# TOP.net
KiCad netlist of a schematic drawn in Altium Designer
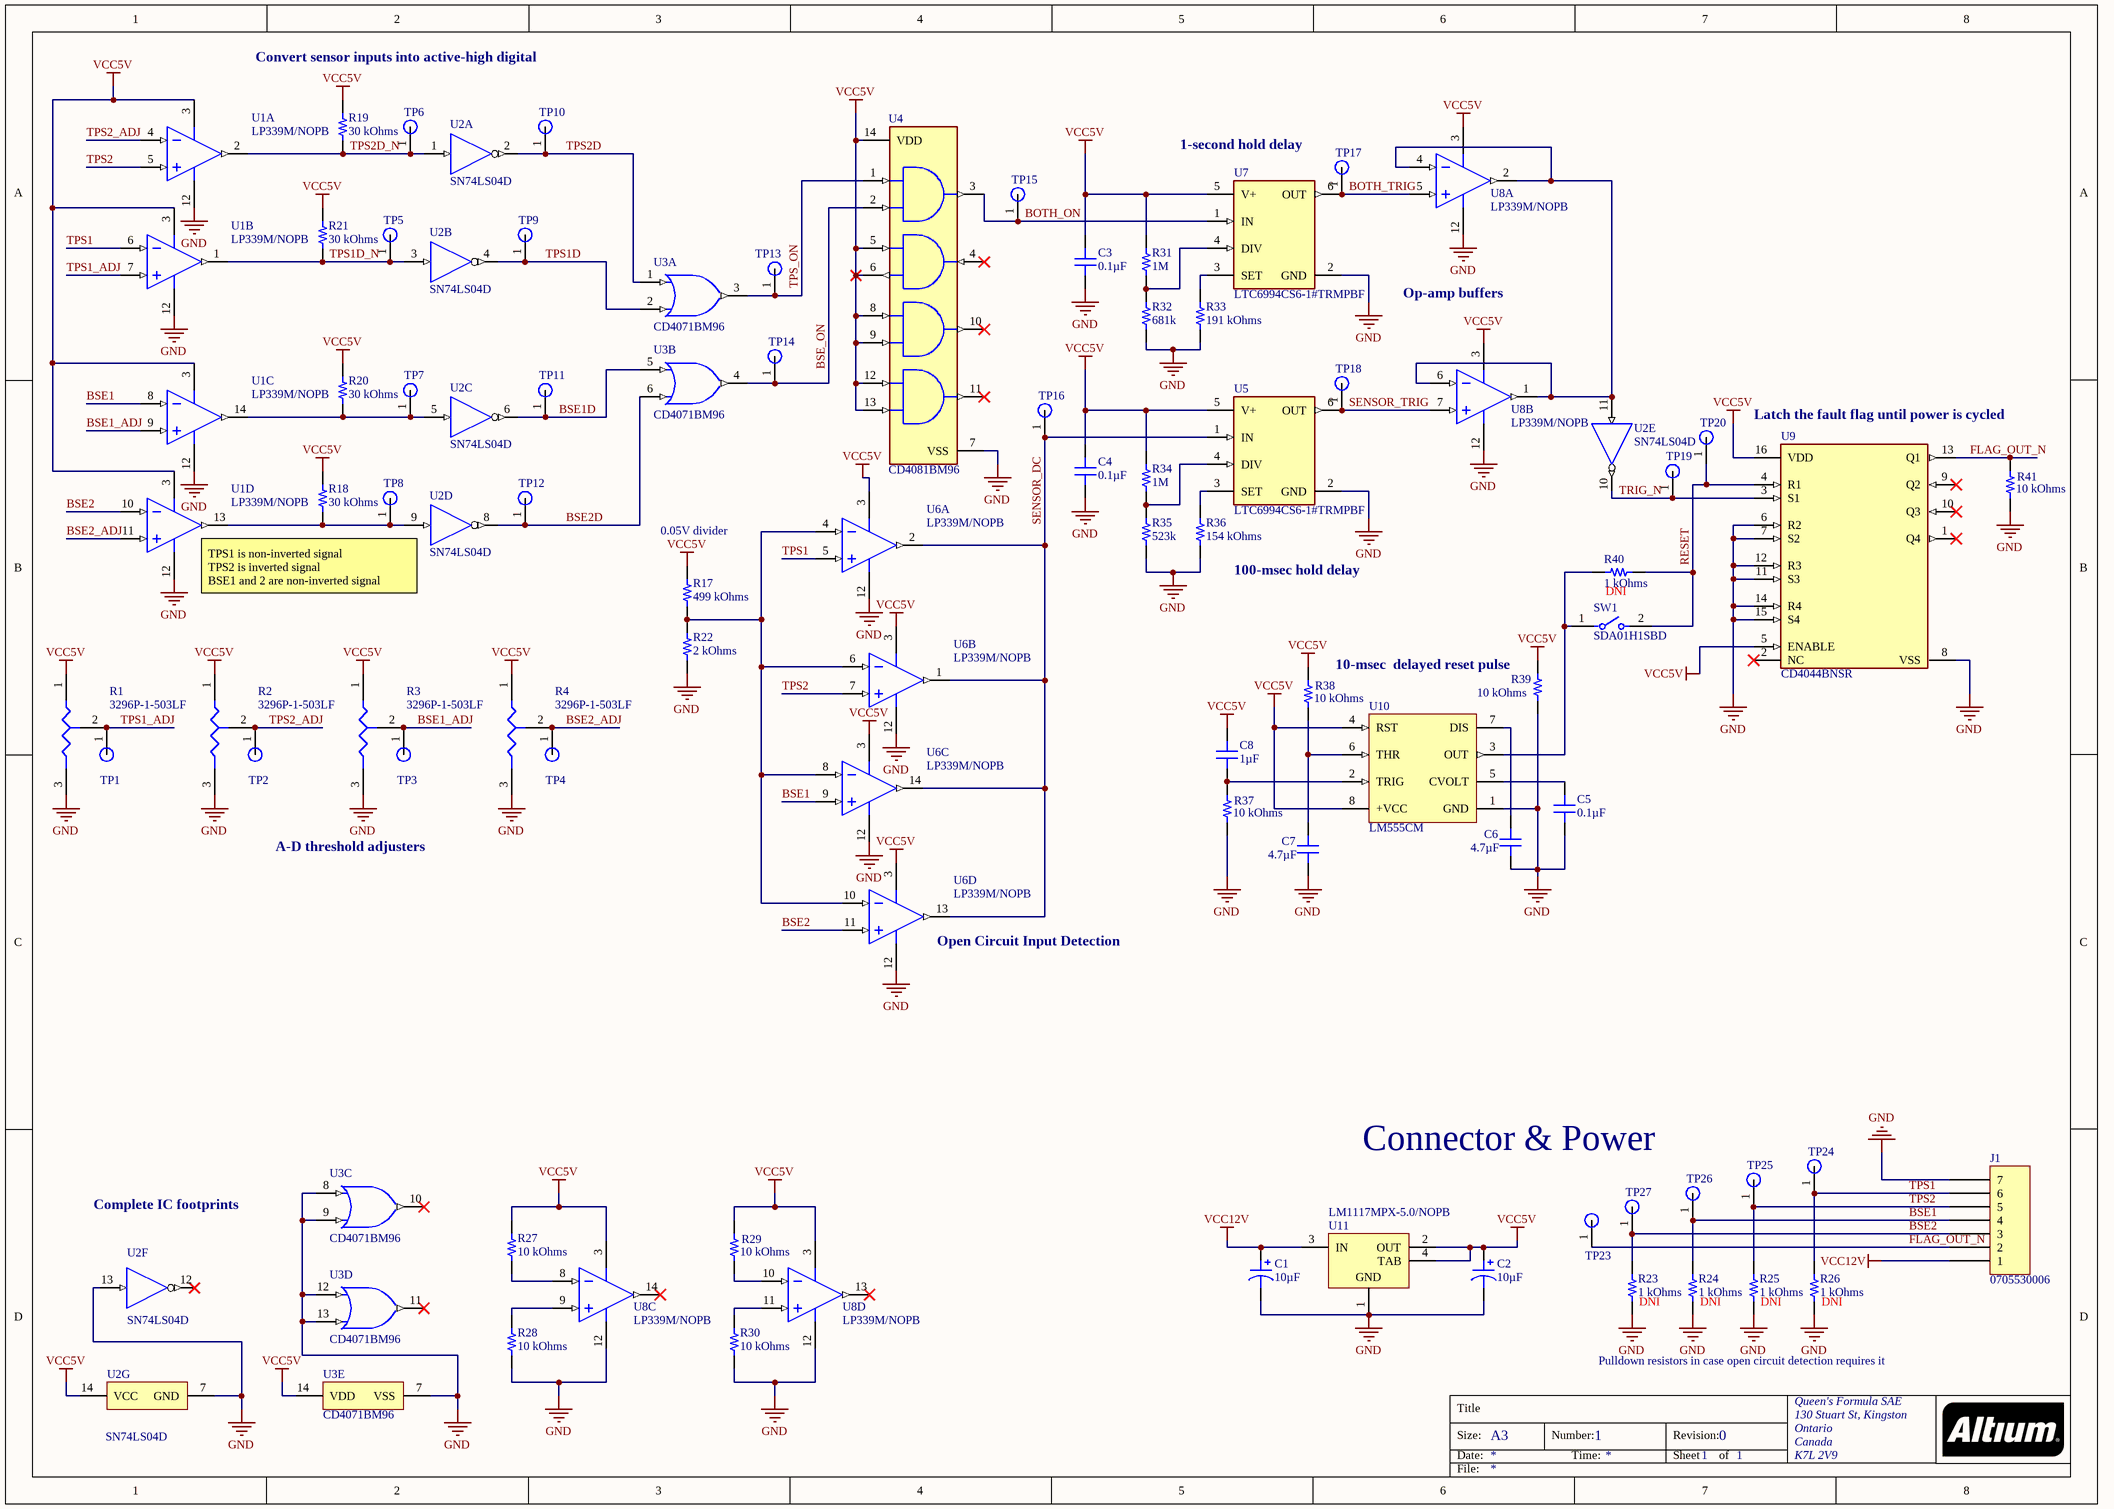
[diagram p0: TOP.SchDoc]

(export (version "E")
  (design (tool "Eeschema 10.0.6"))
  (components
    (comp (ref "C1")
      (value "10µF")
      (footprint "CAP ALSMD 5.3MM H5.4MM")
      (description "CAP ALUM 10UF 20% 50V SMD")
      (fields
        (field (name "PART NUMBER") "EEE-1HA100WR")
        (field (name "MANUFACTURER") "Panasonic Electronic Components")
      )
      (libsource (lib "Celestial Altium Library - altium_library") (part "Polarised Capacitor"))
    )
    (comp (ref "C2")
      (value "10µF")
      (footprint "CAP ALSMD 5.3MM H5.4MM")
      (description "CAP ALUM 10UF 20% 50V SMD")
      (fields
        (field (name "PART NUMBER") "EEE-1HA100WR")
        (field (name "MANUFACTURER") "Panasonic Electronic Components")
      )
      (libsource (lib "Celestial Altium Library - altium_library") (part "Polarised Capacitor"))
    )
    (comp (ref "C3")
      (value "0.1µF")
      (footprint "CAP 0805_2012")
      (description "CAP CER 0.1UF 25V X7R 0805")
      (fields
        (field (name "PART NUMBER") "VJ0805Y104KXXCW1BC")
        (field (name "MANUFACTURER") "Vishay Vitramon")
      )
      (libsource (lib "Celestial Altium Library - altium_library") (part "Capacitor"))
    )
    (comp (ref "C4")
      (value "0.1µF")
      (footprint "CAP 0805_2012")
      (description "CAP CER 0.1UF 25V X7R 0805")
      (fields
        (field (name "PART NUMBER") "VJ0805Y104KXXCW1BC")
        (field (name "MANUFACTURER") "Vishay Vitramon")
      )
      (libsource (lib "Celestial Altium Library - altium_library") (part "Capacitor"))
    )
    (comp (ref "C5")
      (value "0.1µF")
      (footprint "CAP 0805_2012")
      (description "CAP CER 0.1UF 25V X7R 0805")
      (fields
        (field (name "PART NUMBER") "VJ0805Y104KXXCW1BC")
        (field (name "MANUFACTURER") "Vishay Vitramon")
      )
      (libsource (lib "Celestial Altium Library - altium_library") (part "Capacitor"))
    )
    (comp (ref "C6")
      (value "4.7µF")
      (footprint "CAP 0805_2012")
      (description "CAP CER 4.7UF 25V X5R 0805")
      (fields (field (name "PART NUMBER") "TMK212BBJ475KD-T") (field (name "MANUFACTURER") "Taiyo Yuden"))
      (libsource (lib "Celestial Altium Library - altium_library") (part "Capacitor"))
    )
    (comp (ref "C7")
      (value "4.7µF")
      (footprint "CAP 0805_2012")
      (description "CAP CER 4.7UF 25V X5R 0805")
      (fields (field (name "PART NUMBER") "TMK212BBJ475KD-T") (field (name "MANUFACTURER") "Taiyo Yuden"))
      (libsource (lib "Celestial Altium Library - altium_library") (part "Capacitor"))
    )
    (comp (ref "C8")
      (value "1µF")
      (footprint "CAP 0805_2012")
      (description "CAP CER 1UF 25V X7R 0805")
      (fields
        (field (name "PART NUMBER") "VJ0805Y105KXXTW1BC")
        (field (name "MANUFACTURER") "Vishay Vitramon")
      )
      (libsource (lib "Celestial Altium Library - altium_library") (part "Capacitor"))
    )
    (comp (ref "J1")
      (value "0705530006")
      (footprint "MOLEX SDA-70553-7PIN")
      (description "CONN HEADER R/A 7POS 2.54MM")
      (fields (field (name "MANUFACTURER") "Molex"))
      (libsource (lib "Celestial Altium Library - altium_library") (part "7 Pin"))
    )
    (comp (ref "R1")
      (value "3296P-1-503LF")
      (footprint "3296P-1-503LF-Footprint-1")
      (description "50k 10% Trimmer Potentiometer 25-Turn Cermet")
      (fields (field (name "TOLERANCE") "10%"))
      (libsource (lib "Queens University - FSAE") (part "3296P-1-503LF"))
    )
    (comp (ref "R2")
      (value "3296P-1-503LF")
      (footprint "3296P-1-503LF-Footprint-1")
      (description "50k 10% Trimmer Potentiometer 25-Turn Cermet")
      (fields (field (name "TOLERANCE") "10%"))
      (libsource (lib "Queens University - FSAE") (part "3296P-1-503LF"))
    )
    (comp (ref "R3")
      (value "3296P-1-503LF")
      (footprint "3296P-1-503LF-Footprint-1")
      (description "50k 10% Trimmer Potentiometer 25-Turn Cermet")
      (fields (field (name "TOLERANCE") "10%"))
      (libsource (lib "Queens University - FSAE") (part "3296P-1-503LF"))
    )
    (comp (ref "R4")
      (value "3296P-1-503LF")
      (footprint "3296P-1-503LF-Footprint-1")
      (description "50k 10% Trimmer Potentiometer 25-Turn Cermet")
      (fields (field (name "TOLERANCE") "10%"))
      (libsource (lib "Queens University - FSAE") (part "3296P-1-503LF"))
    )
    (comp (ref "R17")
      (value "499 kOhms")
      (footprint "RES 0805_2012")
      (description "RES SMD 499K OHM 1% 1/8W 0805")
      (fields (field (name "PART NUMBER") "RC0805FR-07499KL") (field (name "MANUFACTURER") "Yageo"))
      (libsource (lib "Celestial Altium Library - altium_library") (part "Resistor"))
    )
    (comp (ref "R18")
      (value "30 kOhms")
      (footprint "RES 0805_2012")
      (description "RES SMD 30K OHM 0.5% 1/8W 0805")
      (fields (field (name "PART NUMBER") "RT0805DRD0730KL") (field (name "MANUFACTURER") "Yageo"))
      (libsource (lib "Celestial Altium Library - altium_library") (part "Resistor"))
    )
    (comp (ref "R19")
      (value "30 kOhms")
      (footprint "RES 0805_2012")
      (description "RES SMD 30K OHM 0.5% 1/8W 0805")
      (fields (field (name "PART NUMBER") "RT0805DRD0730KL") (field (name "MANUFACTURER") "Yageo"))
      (libsource (lib "Celestial Altium Library - altium_library") (part "Resistor"))
    )
    (comp (ref "R20")
      (value "30 kOhms")
      (footprint "RES 0805_2012")
      (description "RES SMD 30K OHM 0.5% 1/8W 0805")
      (fields (field (name "PART NUMBER") "RT0805DRD0730KL") (field (name "MANUFACTURER") "Yageo"))
      (libsource (lib "Celestial Altium Library - altium_library") (part "Resistor"))
    )
    (comp (ref "R21")
      (value "30 kOhms")
      (footprint "RES 0805_2012")
      (description "RES SMD 30K OHM 0.5% 1/8W 0805")
      (fields (field (name "PART NUMBER") "RT0805DRD0730KL") (field (name "MANUFACTURER") "Yageo"))
      (libsource (lib "Celestial Altium Library - altium_library") (part "Resistor"))
    )
    (comp (ref "R22")
      (value "2 kOhms")
      (footprint "RES 0805_2012")
      (description "RES SMD 2K OHM 1% 1/8W 0805")
      (fields (field (name "PART NUMBER") "RC0805FR-072KL") (field (name "MANUFACTURER") "Yageo"))
      (libsource (lib "Celestial Altium Library - altium_library") (part "Resistor"))
    )
    (comp (ref "R23")
      (value "1 kOhms")
      (footprint "RES 0805_2012")
      (description "RES 1K OHM 0.1% 1/10W 0805")
      (fields
        (field (name "PART NUMBER") "RNCS0805BKE1K00")
        (field (name "MANUFACTURER") "Stackpole Electronics Inc")
      )
      (libsource (lib "Celestial Altium Library - altium_library") (part "Resistor"))
    )
    (comp (ref "R24")
      (value "1 kOhms")
      (footprint "RES 0805_2012")
      (description "RES 1K OHM 0.1% 1/10W 0805")
      (fields
        (field (name "PART NUMBER") "RNCS0805BKE1K00")
        (field (name "MANUFACTURER") "Stackpole Electronics Inc")
      )
      (libsource (lib "Celestial Altium Library - altium_library") (part "Resistor"))
    )
    (comp (ref "R25")
      (value "1 kOhms")
      (footprint "RES 0805_2012")
      (description "RES 1K OHM 0.1% 1/10W 0805")
      (fields
        (field (name "PART NUMBER") "RNCS0805BKE1K00")
        (field (name "MANUFACTURER") "Stackpole Electronics Inc")
      )
      (libsource (lib "Celestial Altium Library - altium_library") (part "Resistor"))
    )
    (comp (ref "R26")
      (value "1 kOhms")
      (footprint "RES 0805_2012")
      (description "RES 1K OHM 0.1% 1/10W 0805")
      (fields
        (field (name "PART NUMBER") "RNCS0805BKE1K00")
        (field (name "MANUFACTURER") "Stackpole Electronics Inc")
      )
      (libsource (lib "Celestial Altium Library - altium_library") (part "Resistor"))
    )
    (comp (ref "R27")
      (value "10 kOhms")
      (footprint "RES 0805_2012")
      (description "RES SMD 10K OHM 1% 1/8W 0805")
      (fields (field (name "PART NUMBER") "RC0805FR-0710KL") (field (name "MANUFACTURER") "Yageo"))
      (libsource (lib "Celestial Altium Library - altium_library") (part "Resistor"))
    )
    (comp (ref "R28")
      (value "10 kOhms")
      (footprint "RES 0805_2012")
      (description "RES SMD 10K OHM 1% 1/8W 0805")
      (fields (field (name "PART NUMBER") "RC0805FR-0710KL") (field (name "MANUFACTURER") "Yageo"))
      (libsource (lib "Celestial Altium Library - altium_library") (part "Resistor"))
    )
    (comp (ref "R29")
      (value "10 kOhms")
      (footprint "RES 0805_2012")
      (description "RES SMD 10K OHM 1% 1/8W 0805")
      (fields (field (name "PART NUMBER") "RC0805FR-0710KL") (field (name "MANUFACTURER") "Yageo"))
      (libsource (lib "Celestial Altium Library - altium_library") (part "Resistor"))
    )
    (comp (ref "R30")
      (value "10 kOhms")
      (footprint "RES 0805_2012")
      (description "RES SMD 10K OHM 1% 1/8W 0805")
      (fields (field (name "PART NUMBER") "RC0805FR-0710KL") (field (name "MANUFACTURER") "Yageo"))
      (libsource (lib "Celestial Altium Library - altium_library") (part "Resistor"))
    )
    (comp (ref "R31")
      (value "1M")
      (footprint "RES 0805_2012")
      (description "RES SMD 1M OHM 1% 1/8W 0805")
      (fields (field (name "PART NUMBER") "RC0805FR-071ML") (field (name "MANUFACTURER") "Yageo"))
      (libsource (lib "Celestial Altium Library - altium_library") (part "Resistor"))
    )
    (comp (ref "R32")
      (value "681k")
      (footprint "RES 0805_2012")
      (description "RES 681K OHM 1% 1/8W 0805")
      (fields
        (field (name "PART NUMBER") "RMCF0805FT681K")
        (field (name "MANUFACTURER") "Stackpole Electronics Inc")
      )
      (libsource (lib "Celestial Altium Library - altium_library") (part "Resistor"))
    )
    (comp (ref "R33")
      (value "191 kOhms")
      (footprint "RES 0805_2012")
      (description "RES SMD 191K OHM 1% 1/8W 0805")
      (fields (field (name "PART NUMBER") "RC0805FR-07191KL") (field (name "MANUFACTURER") "Yageo"))
      (libsource (lib "Celestial Altium Library - altium_library") (part "Resistor"))
    )
    (comp (ref "R34")
      (value "1M")
      (footprint "RES 0805_2012")
      (description "RES SMD 1M OHM 1% 1/8W 0805")
      (fields (field (name "PART NUMBER") "RC0805FR-071ML") (field (name "MANUFACTURER") "Yageo"))
      (libsource (lib "Celestial Altium Library - altium_library") (part "Resistor"))
    )
    (comp (ref "R35")
      (value "523k")
      (footprint "RES 0805_2012")
      (description "RES SMD 523K OHM 1% 1/8W 0805")
      (fields (field (name "PART NUMBER") "RC0805FR-07523KL") (field (name "MANUFACTURER") "Yageo"))
      (libsource (lib "Celestial Altium Library - altium_library") (part "Resistor"))
    )
    (comp (ref "R36")
      (value "154 kOhms")
      (footprint "RES 0805_2012")
      (description "RES SMD 154K OHM 1% 1/8W 0805")
      (fields (field (name "PART NUMBER") "RC0805FR-07154KL") (field (name "MANUFACTURER") "Yageo"))
      (libsource (lib "Celestial Altium Library - altium_library") (part "Resistor"))
    )
    (comp (ref "R37")
      (value "10 kOhms")
      (footprint "RES 0805_2012")
      (description "RES SMD 10K OHM 1% 1/8W 0805")
      (fields (field (name "PART NUMBER") "RC0805FR-0710KL") (field (name "MANUFACTURER") "Yageo"))
      (libsource (lib "Celestial Altium Library - altium_library") (part "Resistor"))
    )
    (comp (ref "R38")
      (value "10 kOhms")
      (footprint "RES 0805_2012")
      (description "RES SMD 10K OHM 1% 1/8W 0805")
      (fields (field (name "PART NUMBER") "RC0805FR-0710KL") (field (name "MANUFACTURER") "Yageo"))
      (libsource (lib "Celestial Altium Library - altium_library") (part "Resistor"))
    )
    (comp (ref "R39")
      (value "10 kOhms")
      (footprint "RES 0805_2012")
      (description "RES SMD 10K OHM 1% 1/8W 0805")
      (fields (field (name "PART NUMBER") "RC0805FR-0710KL") (field (name "MANUFACTURER") "Yageo"))
      (libsource (lib "Celestial Altium Library - altium_library") (part "Resistor"))
    )
    (comp (ref "R40")
      (value "1 kOhms")
      (footprint "RES 0805_2012")
      (description "RES 1K OHM 0.1% 1/10W 0805")
      (fields
        (field (name "PART NUMBER") "RNCS0805BKE1K00")
        (field (name "MANUFACTURER") "Stackpole Electronics Inc")
      )
      (libsource (lib "Celestial Altium Library - altium_library") (part "Resistor"))
    )
    (comp (ref "R41")
      (value "10 kOhms")
      (footprint "RES 0805_2012")
      (description "RES SMD 10K OHM 1% 1/8W 0805")
      (fields (field (name "PART NUMBER") "RC0805FR-0710KL") (field (name "MANUFACTURER") "Yageo"))
      (libsource (lib "Celestial Altium Library - altium_library") (part "Resistor"))
    )
    (comp (ref "SW1")
      (value "SDA01H1SBD")
      (footprint "FP-SDA01H1SBD-MFG")
      (description "Switch DIP OFF ON SPST 1 Raised Slide 0.1A 24VDC Gull Wing 1000Cycles SMD Tube")
      (libsource (lib "Queens University - FSAE") (part "bb27bde45df87f1f469753f287ef5ae"))
    )
    (comp (ref "TP1") (value "Test Point") (footprint "TP1") (libsource (lib "ethan") (part "TP1")))
    (comp (ref "TP2") (value "Test Point") (footprint "TP1") (libsource (lib "ethan") (part "TP1")))
    (comp (ref "TP3") (value "Test Point") (footprint "TP1") (libsource (lib "ethan") (part "TP1")))
    (comp (ref "TP4") (value "Test Point") (footprint "TP1") (libsource (lib "ethan") (part "TP1")))
    (comp (ref "TP5") (value "Test Point") (footprint "TP1") (libsource (lib "ethan") (part "TP1")))
    (comp (ref "TP6") (value "Test Point") (footprint "TP1") (libsource (lib "ethan") (part "TP1")))
    (comp (ref "TP7") (value "Test Point") (footprint "TP1") (libsource (lib "ethan") (part "TP1")))
    (comp (ref "TP8") (value "Test Point") (footprint "TP1") (libsource (lib "ethan") (part "TP1")))
    (comp (ref "TP9") (value "Test Point") (footprint "TP1") (libsource (lib "ethan") (part "TP1")))
    (comp (ref "TP10") (value "Test Point") (footprint "TP1") (libsource (lib "ethan") (part "TP1")))
    (comp (ref "TP11") (value "Test Point") (footprint "TP1") (libsource (lib "ethan") (part "TP1")))
    (comp (ref "TP12") (value "Test Point") (footprint "TP1") (libsource (lib "ethan") (part "TP1")))
    (comp (ref "TP13") (value "Test Point") (footprint "TP1") (libsource (lib "ethan") (part "TP1")))
    (comp (ref "TP14") (value "Test Point") (footprint "TP1") (libsource (lib "ethan") (part "TP1")))
    (comp (ref "TP15") (value "Test Point") (footprint "TP1") (libsource (lib "ethan") (part "TP1")))
    (comp (ref "TP16") (value "Test Point") (footprint "TP1") (libsource (lib "ethan") (part "TP1")))
    (comp (ref "TP17") (value "Test Point") (footprint "TP1") (libsource (lib "ethan") (part "TP1")))
    (comp (ref "TP18") (value "Test Point") (footprint "TP1") (libsource (lib "ethan") (part "TP1")))
    (comp (ref "TP19") (value "Test Point") (footprint "TP1") (libsource (lib "ethan") (part "TP1")))
    (comp (ref "TP20") (value "Test Point") (footprint "TP1") (libsource (lib "ethan") (part "TP1")))
    (comp (ref "TP23") (value "Test Point") (footprint "TP1") (libsource (lib "ethan") (part "TP1")))
    (comp (ref "TP24") (value "Test Point") (footprint "TP1") (libsource (lib "ethan") (part "TP1")))
    (comp (ref "TP25") (value "Test Point") (footprint "TP1") (libsource (lib "ethan") (part "TP1")))
    (comp (ref "TP26") (value "Test Point") (footprint "TP1") (libsource (lib "ethan") (part "TP1")))
    (comp (ref "TP27") (value "Test Point") (footprint "TP1") (libsource (lib "ethan") (part "TP1")))
    (comp (ref "U1")
      (value "LP339M/NOPB")
      (footprint "D0014A_L")
      (description "TEXAS INSTRUMENTS   LP339M/NOPB   LOW POWER COMPARATOR, QUAD, 8 uS, SOIC-14")
      (libsource (lib "Queens University - FSAE") (part "AN-COMP-LP339-14"))
    )
    (comp (ref "U2")
      (value "SN74LS04D")
      (footprint "D0014A_L")
      (description "TEXAS INSTRUMENTS - SN74LS04D - HEX INVERTER, SMD, 74LS04, SOIC14")
      (libsource (lib "Queens University - FSAE") (part "TI-CD_SNX4XXXXXX4X_19A-14"))
    )
    (comp (ref "U3")
      (value "CD4071BM96")
      (footprint "D0014A_L")
      (description "OR Gate 4-Element 2-IN CMOS 14-Pin SOIC T/R")
      (libsource (lib "Queens University - FSAE") (part "TI-CD4071B-14"))
    )
    (comp (ref "U4")
      (value "CD4081BM96")
      (footprint "FP-D0014A-MFG")
      (description "TEXAS INSTRUMENTS - CD4081BM96 - AND Gate, CD4081, 8 Input, 6.8 mA, 3 V to 18 V, SOIC-14")
      (libsource (lib "Queens University - FSAE") (part "72f76806fbbab040b8a954f50d4bcdd"))
    )
    (comp (ref "U5")
      (value "LTC6994CS6-1#TRMPBF")
      (footprint "FP-S6-6-05-08-1636-MFG")
      (description "Programmable Delay Block 6-Pin TSOT-23 T/R")
      (libsource (lib "Queens University - FSAE") (part "9980ea3ec28f5fc7ab7b696581a065a"))
    )
    (comp (ref "U6")
      (value "LP339M/NOPB")
      (footprint "D0014A_L")
      (description "TEXAS INSTRUMENTS   LP339M/NOPB   LOW POWER COMPARATOR, QUAD, 8 uS, SOIC-14")
      (libsource (lib "Queens University - FSAE") (part "AN-COMP-LP339-14"))
    )
    (comp (ref "U7")
      (value "LTC6994CS6-1#TRMPBF")
      (footprint "FP-S6-6-05-08-1636-MFG")
      (description "Programmable Delay Block 6-Pin TSOT-23 T/R")
      (libsource (lib "Queens University - FSAE") (part "9980ea3ec28f5fc7ab7b696581a065a"))
    )
    (comp (ref "U8")
      (value "LP339M/NOPB")
      (footprint "D0014A_L")
      (description "TEXAS INSTRUMENTS   LP339M/NOPB   LOW POWER COMPARATOR, QUAD, 8 uS, SOIC-14")
      (libsource (lib "Queens University - FSAE") (part "AN-COMP-LP339-14"))
    )
    (comp (ref "U9")
      (value "CD4044BNSR")
      (footprint "FP-D0016A-MFG")
      (libsource (lib "Queens University - FSAE") (part "b654bc9f5570033e531f2d9d884d1b2"))
    )
    (comp (ref "U10")
      (value "LM555CM")
      (footprint "D0008A_L")
      (description "IC OSC SGL TIMER 100KHZ 8-SOIC")
      (libsource (lib "Queens University - FSAE") (part "AN-TIMER-LM555-8"))
    )
    (comp (ref "U11")
      (value "LM1117MPX-5.0/NOPB")
      (footprint "DCY0004A_M")
      (description "800-mA 15-V linear voltage regulator 4-SOT-223 0 to 125")
      (libsource (lib "Queens University - FSAE") (part "PM-REG-LM1086-SOT4"))
    )
  )
  (nets
    (net (code "1") (name "/BOTH_ON") (class "Default")
      (node (ref "TP15") (pin "1") (pinfunction "1_1") (pintype "passive"))
      (node (ref "U4") (pin "3") (pinfunction "J_3") (pintype "output"))
      (node (ref "U7") (pin "1") (pinfunction "IN_1") (pintype "input"))
    )
    (net (code "2") (name "/BOTH_TRIG") (class "Default")
      (node (ref "TP17") (pin "1") (pinfunction "1_1") (pintype "passive"))
      (node (ref "U7") (pin "6") (pinfunction "OUT_6") (pintype "output"))
      (node (ref "U8") (pin "5") (pinfunction "IN1+_5") (pintype "input"))
    )
    (net (code "3") (name "/BSE1") (class "Default")
      (node (ref "J1") (pin "4") (pinfunction "4_4") (pintype "passive"))
      (node (ref "R24") (pin "2") (pinfunction "2_2") (pintype "passive"))
      (node (ref "TP26") (pin "1") (pinfunction "1_1") (pintype "passive"))
      (node (ref "U1") (pin "8") (pinfunction "IN3-_8") (pintype "input"))
      (node (ref "U6") (pin "9") (pinfunction "IN3+_9") (pintype "input"))
    )
    (net (code "4") (name "/BSE1D") (class "Default")
      (node (ref "TP11") (pin "1") (pinfunction "1_1") (pintype "passive"))
      (node (ref "U2") (pin "6") (pinfunction "~{3Y}_6") (pintype "output"))
      (node (ref "U3") (pin "5") (pinfunction "C_5") (pintype "input"))
    )
    (net (code "5") (name "/BSE1_ADJ") (class "Default")
      (node (ref "R3") (pin "2") (pinfunction "TAP_2") (pintype "passive"))
      (node (ref "TP3") (pin "1") (pinfunction "1_1") (pintype "passive"))
      (node (ref "U1") (pin "9") (pinfunction "IN3+_9") (pintype "input"))
    )
    (net (code "6") (name "/BSE2") (class "Default")
      (node (ref "J1") (pin "3") (pinfunction "3_3") (pintype "passive"))
      (node (ref "R23") (pin "2") (pinfunction "2_2") (pintype "passive"))
      (node (ref "TP27") (pin "1") (pinfunction "1_1") (pintype "passive"))
      (node (ref "U1") (pin "10") (pinfunction "IN4-_10") (pintype "input"))
      (node (ref "U6") (pin "11") (pinfunction "IN4+_11") (pintype "input"))
    )
    (net (code "7") (name "/BSE2D") (class "Default")
      (node (ref "TP12") (pin "1") (pinfunction "1_1") (pintype "passive"))
      (node (ref "U2") (pin "8") (pinfunction "~{4Y}_8") (pintype "output"))
      (node (ref "U3") (pin "6") (pinfunction "D_6") (pintype "input"))
    )
    (net (code "8") (name "/BSE2_ADJ") (class "Default")
      (node (ref "R4") (pin "2") (pinfunction "TAP_2") (pintype "passive"))
      (node (ref "TP4") (pin "1") (pinfunction "1_1") (pintype "passive"))
      (node (ref "U1") (pin "11") (pinfunction "IN4+_11") (pintype "input"))
    )
    (net (code "9") (name "/BSE_ON") (class "Default")
      (node (ref "TP14") (pin "1") (pinfunction "1_1") (pintype "passive"))
      (node (ref "U3") (pin "4") (pinfunction "K_4") (pintype "output"))
      (node (ref "U4") (pin "2") (pinfunction "B_2") (pintype "input"))
    )
    (net (code "10") (name "/FLAG_OUT_N") (class "Default")
      (node (ref "J1") (pin "2") (pinfunction "2_2") (pintype "passive"))
      (node (ref "R41") (pin "2") (pinfunction "2_2") (pintype "passive"))
      (node (ref "TP23") (pin "1") (pinfunction "1_1") (pintype "passive"))
      (node (ref "U9") (pin "13") (pinfunction "Q1_13") (pintype "output"))
    )
    (net (code "11") (name "/RESET") (class "Default")
      (node (ref "R40") (pin "1") (pinfunction "1_1") (pintype "passive"))
      (node (ref "SW1") (pin "2") (pinfunction "2_2") (pintype "passive"))
      (node (ref "TP20") (pin "1") (pinfunction "1_1") (pintype "passive"))
      (node (ref "U9") (pin "4") (pinfunction "R1_4") (pintype "input"))
    )
    (net (code "12") (name "/SENSOR_DC") (class "Default")
      (node (ref "TP16") (pin "1") (pinfunction "1_1") (pintype "passive"))
      (node (ref "U5") (pin "1") (pinfunction "IN_1") (pintype "input"))
      (node (ref "U6") (pin "1") (pinfunction "OUT2_1") (pintype "output"))
      (node (ref "U6") (pin "13") (pinfunction "OUT4_13") (pintype "output"))
      (node (ref "U6") (pin "14") (pinfunction "OUT3_14") (pintype "output"))
      (node (ref "U6") (pin "2") (pinfunction "OUT1_2") (pintype "output"))
    )
    (net (code "13") (name "/SENSOR_TRIG") (class "Default")
      (node (ref "TP18") (pin "1") (pinfunction "1_1") (pintype "passive"))
      (node (ref "U5") (pin "6") (pinfunction "OUT_6") (pintype "output"))
      (node (ref "U8") (pin "7") (pinfunction "IN2+_7") (pintype "input"))
    )
    (net (code "14") (name "/TPS1") (class "Default")
      (node (ref "J1") (pin "6") (pinfunction "6_6") (pintype "passive"))
      (node (ref "R26") (pin "2") (pinfunction "2_2") (pintype "passive"))
      (node (ref "TP24") (pin "1") (pinfunction "1_1") (pintype "passive"))
      (node (ref "U1") (pin "6") (pinfunction "IN2-_6") (pintype "input"))
      (node (ref "U6") (pin "5") (pinfunction "IN1+_5") (pintype "input"))
    )
    (net (code "15") (name "/TPS1D") (class "Default")
      (node (ref "TP9") (pin "1") (pinfunction "1_1") (pintype "passive"))
      (node (ref "U2") (pin "4") (pinfunction "~{2Y}_4") (pintype "output"))
      (node (ref "U3") (pin "2") (pinfunction "B_2") (pintype "input"))
    )
    (net (code "16") (name "/TPS1D_N") (class "Default")
      (node (ref "R21") (pin "1") (pinfunction "1_1") (pintype "passive"))
      (node (ref "TP5") (pin "1") (pinfunction "1_1") (pintype "passive"))
      (node (ref "U1") (pin "1") (pinfunction "OUT2_1") (pintype "output"))
      (node (ref "U2") (pin "3") (pinfunction "2A_3") (pintype "input"))
    )
    (net (code "17") (name "/TPS1_ADJ") (class "Default")
      (node (ref "R1") (pin "2") (pinfunction "TAP_2") (pintype "passive"))
      (node (ref "TP1") (pin "1") (pinfunction "1_1") (pintype "passive"))
      (node (ref "U1") (pin "7") (pinfunction "IN2+_7") (pintype "input"))
    )
    (net (code "18") (name "/TPS2") (class "Default")
      (node (ref "J1") (pin "5") (pinfunction "5_5") (pintype "passive"))
      (node (ref "R25") (pin "2") (pinfunction "2_2") (pintype "passive"))
      (node (ref "TP25") (pin "1") (pinfunction "1_1") (pintype "passive"))
      (node (ref "U1") (pin "5") (pinfunction "IN1+_5") (pintype "input"))
      (node (ref "U6") (pin "7") (pinfunction "IN2+_7") (pintype "input"))
    )
    (net (code "19") (name "/TPS2D") (class "Default")
      (node (ref "TP10") (pin "1") (pinfunction "1_1") (pintype "passive"))
      (node (ref "U2") (pin "2") (pinfunction "~{1Y}_2") (pintype "output"))
      (node (ref "U3") (pin "1") (pinfunction "A_1") (pintype "input"))
    )
    (net (code "20") (name "/TPS2D_N") (class "Default")
      (node (ref "R19") (pin "1") (pinfunction "1_1") (pintype "passive"))
      (node (ref "TP6") (pin "1") (pinfunction "1_1") (pintype "passive"))
      (node (ref "U1") (pin "2") (pinfunction "OUT1_2") (pintype "output"))
      (node (ref "U2") (pin "1") (pinfunction "1A_1") (pintype "input"))
    )
    (net (code "21") (name "/TPS2_ADJ") (class "Default")
      (node (ref "R2") (pin "2") (pinfunction "TAP_2") (pintype "passive"))
      (node (ref "TP2") (pin "1") (pinfunction "1_1") (pintype "passive"))
      (node (ref "U1") (pin "4") (pinfunction "IN1-_4") (pintype "input"))
    )
    (net (code "22") (name "/TPS_ON") (class "Default")
      (node (ref "TP13") (pin "1") (pinfunction "1_1") (pintype "passive"))
      (node (ref "U3") (pin "3") (pinfunction "J_3") (pintype "output"))
      (node (ref "U4") (pin "1") (pinfunction "A_1") (pintype "input"))
    )
    (net (code "23") (name "/TRIG_N") (class "Default")
      (node (ref "TP19") (pin "1") (pinfunction "1_1") (pintype "passive"))
      (node (ref "U2") (pin "10") (pinfunction "~{5Y}_10") (pintype "output"))
      (node (ref "U9") (pin "3") (pinfunction "S1_3") (pintype "input"))
    )
    (net (code "24") (name "GND") (class "Default")
      (node (ref "C1") (pin "2") (pinfunction "2_2") (pintype "passive"))
      (node (ref "C2") (pin "2") (pinfunction "2_2") (pintype "passive"))
      (node (ref "C3") (pin "1") (pinfunction "1_1") (pintype "passive"))
      (node (ref "C4") (pin "1") (pinfunction "1_1") (pintype "passive"))
      (node (ref "C5") (pin "1") (pinfunction "1_1") (pintype "passive"))
      (node (ref "C6") (pin "2") (pinfunction "2_2") (pintype "passive"))
      (node (ref "C7") (pin "2") (pinfunction "2_2") (pintype "passive"))
      (node (ref "J1") (pin "7") (pinfunction "7_7") (pintype "passive"))
      (node (ref "R1") (pin "3") (pinfunction "B_3") (pintype "passive"))
      (node (ref "R2") (pin "3") (pinfunction "B_3") (pintype "passive"))
      (node (ref "R22") (pin "1") (pinfunction "1_1") (pintype "passive"))
      (node (ref "R23") (pin "1") (pinfunction "1_1") (pintype "passive"))
      (node (ref "R24") (pin "1") (pinfunction "1_1") (pintype "passive"))
      (node (ref "R25") (pin "1") (pinfunction "1_1") (pintype "passive"))
      (node (ref "R26") (pin "1") (pinfunction "1_1") (pintype "passive"))
      (node (ref "R28") (pin "1") (pinfunction "1_1") (pintype "passive"))
      (node (ref "R3") (pin "3") (pinfunction "B_3") (pintype "passive"))
      (node (ref "R30") (pin "1") (pinfunction "1_1") (pintype "passive"))
      (node (ref "R32") (pin "1") (pinfunction "1_1") (pintype "passive"))
      (node (ref "R33") (pin "1") (pinfunction "1_1") (pintype "passive"))
      (node (ref "R35") (pin "1") (pinfunction "1_1") (pintype "passive"))
      (node (ref "R36") (pin "1") (pinfunction "1_1") (pintype "passive"))
      (node (ref "R37") (pin "1") (pinfunction "1_1") (pintype "passive"))
      (node (ref "R39") (pin "1") (pinfunction "1_1") (pintype "passive"))
      (node (ref "R4") (pin "3") (pinfunction "B_3") (pintype "passive"))
      (node (ref "R41") (pin "1") (pinfunction "1_1") (pintype "passive"))
      (node (ref "U1") (pin "12") (pinfunction "GND_12") (pintype "power_in"))
      (node (ref "U10") (pin "1") (pinfunction "GND_1") (pintype "power_in"))
      (node (ref "U11") (pin "1") (pinfunction "GND_1") (pintype "power_in"))
      (node (ref "U2") (pin "13") (pinfunction "6A_13") (pintype "input"))
      (node (ref "U2") (pin "7") (pinfunction "GND_7") (pintype "power_in"))
      (node (ref "U3") (pin "12") (pinfunction "G_12") (pintype "input"))
      (node (ref "U3") (pin "13") (pinfunction "H_13") (pintype "input"))
      (node (ref "U3") (pin "7") (pinfunction "VSS_7") (pintype "power_in"))
      (node (ref "U3") (pin "8") (pinfunction "E_8") (pintype "input"))
      (node (ref "U3") (pin "9") (pinfunction "F_9") (pintype "input"))
      (node (ref "U4") (pin "7") (pinfunction "VSS_7") (pintype "power_in"))
      (node (ref "U5") (pin "2") (pinfunction "GND_2") (pintype "power_in"))
      (node (ref "U6") (pin "12") (pinfunction "GND_12") (pintype "power_in"))
      (node (ref "U7") (pin "2") (pinfunction "GND_2") (pintype "power_in"))
      (node (ref "U8") (pin "12") (pinfunction "GND_12") (pintype "power_in"))
      (node (ref "U9") (pin "11") (pinfunction "S3_11") (pintype "input"))
      (node (ref "U9") (pin "12") (pinfunction "R3_12") (pintype "input"))
      (node (ref "U9") (pin "14") (pinfunction "R4_14") (pintype "input"))
      (node (ref "U9") (pin "15") (pinfunction "S4_15") (pintype "input"))
      (node (ref "U9") (pin "6") (pinfunction "R2_6") (pintype "input"))
      (node (ref "U9") (pin "7") (pinfunction "S2_7") (pintype "input"))
      (node (ref "U9") (pin "8") (pinfunction "VSS_8") (pintype "power_in"))
    )
    (net (code "25") (name "Net-(U1C-OUT3)") (class "Default")
      (node (ref "R20") (pin "1") (pinfunction "1_1") (pintype "passive"))
      (node (ref "TP7") (pin "1") (pinfunction "1_1") (pintype "passive"))
      (node (ref "U1") (pin "14") (pinfunction "OUT3_14") (pintype "output"))
      (node (ref "U2") (pin "5") (pinfunction "3A_5") (pintype "input"))
    )
    (net (code "26") (name "Net-(U1D-OUT4)") (class "Default")
      (node (ref "R18") (pin "1") (pinfunction "1_1") (pintype "passive"))
      (node (ref "TP8") (pin "1") (pinfunction "1_1") (pintype "passive"))
      (node (ref "U1") (pin "13") (pinfunction "OUT4_13") (pintype "output"))
      (node (ref "U2") (pin "9") (pinfunction "4A_9") (pintype "input"))
    )
    (net (code "27") (name "Net-(U2E-5A)") (class "Default")
      (node (ref "U2") (pin "11") (pinfunction "5A_11") (pintype "input"))
      (node (ref "U8") (pin "1") (pinfunction "OUT2_1") (pintype "output"))
      (node (ref "U8") (pin "2") (pinfunction "OUT1_2") (pintype "output"))
      (node (ref "U8") (pin "4") (pinfunction "IN1-_4") (pintype "input"))
      (node (ref "U8") (pin "6") (pinfunction "IN2-_6") (pintype "input"))
    )
    (net (code "28") (name "Net-(U5-DIV)") (class "Default")
      (node (ref "R34") (pin "2") (pinfunction "2_2") (pintype "passive"))
      (node (ref "R35") (pin "2") (pinfunction "2_2") (pintype "passive"))
      (node (ref "U5") (pin "4") (pinfunction "DIV_4") (pintype "input"))
    )
    (net (code "29") (name "Net-(U5-SET)") (class "Default")
      (node (ref "R36") (pin "2") (pinfunction "2_2") (pintype "passive"))
      (node (ref "U5") (pin "3") (pinfunction "SET_3") (pintype "passive"))
    )
    (net (code "30") (name "Net-(U6A-IN1-)") (class "Default")
      (node (ref "R17") (pin "1") (pinfunction "1_1") (pintype "passive"))
      (node (ref "R22") (pin "2") (pinfunction "2_2") (pintype "passive"))
      (node (ref "U6") (pin "10") (pinfunction "IN4-_10") (pintype "input"))
      (node (ref "U6") (pin "4") (pinfunction "IN1-_4") (pintype "input"))
      (node (ref "U6") (pin "6") (pinfunction "IN2-_6") (pintype "input"))
      (node (ref "U6") (pin "8") (pinfunction "IN3-_8") (pintype "input"))
    )
    (net (code "31") (name "Net-(U7-DIV)") (class "Default")
      (node (ref "R31") (pin "2") (pinfunction "2_2") (pintype "passive"))
      (node (ref "R32") (pin "2") (pinfunction "2_2") (pintype "passive"))
      (node (ref "U7") (pin "4") (pinfunction "DIV_4") (pintype "input"))
    )
    (net (code "32") (name "Net-(U7-SET)") (class "Default")
      (node (ref "R33") (pin "2") (pinfunction "2_2") (pintype "passive"))
      (node (ref "U7") (pin "3") (pinfunction "SET_3") (pintype "passive"))
    )
    (net (code "33") (name "Net-(U8C-IN3+)") (class "Default")
      (node (ref "R28") (pin "2") (pinfunction "2_2") (pintype "passive"))
      (node (ref "U8") (pin "9") (pinfunction "IN3+_9") (pintype "input"))
    )
    (net (code "34") (name "Net-(U8C-IN3-)") (class "Default")
      (node (ref "R27") (pin "1") (pinfunction "1_1") (pintype "passive"))
      (node (ref "U8") (pin "8") (pinfunction "IN3-_8") (pintype "input"))
    )
    (net (code "35") (name "Net-(U8D-IN4+)") (class "Default")
      (node (ref "R30") (pin "2") (pinfunction "2_2") (pintype "passive"))
      (node (ref "U8") (pin "11") (pinfunction "IN4+_11") (pintype "input"))
    )
    (net (code "36") (name "Net-(U8D-IN4-)") (class "Default")
      (node (ref "R29") (pin "1") (pinfunction "1_1") (pintype "passive"))
      (node (ref "U8") (pin "10") (pinfunction "IN4-_10") (pintype "input"))
    )
    (net (code "37") (name "Net-(U10-CVOLT)") (class "Default")
      (node (ref "C5") (pin "2") (pinfunction "2_2") (pintype "passive"))
      (node (ref "U10") (pin "5") (pinfunction "CVOLT_5") (pintype "passive"))
    )
    (net (code "38") (name "Net-(U10-DIS)") (class "Default")
      (node (ref "C6") (pin "1") (pinfunction "1_1") (pintype "passive"))
      (node (ref "U10") (pin "7") (pinfunction "DIS_7") (pintype "open_collector"))
    )
    (net (code "39") (name "Net-(U10-OUT)") (class "Default")
      (node (ref "R40") (pin "2") (pinfunction "2_2") (pintype "passive"))
      (node (ref "SW1") (pin "1") (pinfunction "1_1") (pintype "passive"))
      (node (ref "U10") (pin "3") (pinfunction "OUT_3") (pintype "output"))
    )
    (net (code "40") (name "Net-(U10-THR)") (class "Default")
      (node (ref "C7") (pin "1") (pinfunction "1_1") (pintype "passive"))
      (node (ref "R38") (pin "1") (pinfunction "1_1") (pintype "passive"))
      (node (ref "U10") (pin "6") (pinfunction "THR_6") (pintype "input"))
    )
    (net (code "41") (name "Net-(U10-TRIG)") (class "Default")
      (node (ref "C8") (pin "1") (pinfunction "1_1") (pintype "passive"))
      (node (ref "R37") (pin "2") (pinfunction "2_2") (pintype "passive"))
      (node (ref "U10") (pin "2") (pinfunction "TRIG_2") (pintype "input"))
    )
    (net (code "42") (name "VCC5V") (class "Default")
      (node (ref "C2") (pin "1") (pinfunction "1_1") (pintype "passive"))
      (node (ref "C3") (pin "2") (pinfunction "2_2") (pintype "passive"))
      (node (ref "C4") (pin "2") (pinfunction "2_2") (pintype "passive"))
      (node (ref "C8") (pin "2") (pinfunction "2_2") (pintype "passive"))
      (node (ref "R1") (pin "1") (pinfunction "A_1") (pintype "passive"))
      (node (ref "R17") (pin "2") (pinfunction "2_2") (pintype "passive"))
      (node (ref "R18") (pin "2") (pinfunction "2_2") (pintype "passive"))
      (node (ref "R19") (pin "2") (pinfunction "2_2") (pintype "passive"))
      (node (ref "R2") (pin "1") (pinfunction "A_1") (pintype "passive"))
      (node (ref "R20") (pin "2") (pinfunction "2_2") (pintype "passive"))
      (node (ref "R21") (pin "2") (pinfunction "2_2") (pintype "passive"))
      (node (ref "R27") (pin "2") (pinfunction "2_2") (pintype "passive"))
      (node (ref "R29") (pin "2") (pinfunction "2_2") (pintype "passive"))
      (node (ref "R3") (pin "1") (pinfunction "A_1") (pintype "passive"))
      (node (ref "R31") (pin "1") (pinfunction "1_1") (pintype "passive"))
      (node (ref "R34") (pin "1") (pinfunction "1_1") (pintype "passive"))
      (node (ref "R38") (pin "2") (pinfunction "2_2") (pintype "passive"))
      (node (ref "R39") (pin "2") (pinfunction "2_2") (pintype "passive"))
      (node (ref "R4") (pin "1") (pinfunction "A_1") (pintype "passive"))
      (node (ref "U1") (pin "3") (pinfunction "V+_3") (pintype "power_in"))
      (node (ref "U10") (pin "4") (pinfunction "RST_4") (pintype "input"))
      (node (ref "U10") (pin "8") (pinfunction "+VCC_8") (pintype "power_in"))
      (node (ref "U11") (pin "2") (pinfunction "OUT_2") (pintype "power_in"))
      (node (ref "U11") (pin "4") (pinfunction "TAB_4") (pintype "power_in"))
      (node (ref "U2") (pin "14") (pinfunction "VCC_14") (pintype "power_in"))
      (node (ref "U3") (pin "14") (pinfunction "VDD_14") (pintype "power_in"))
      (node (ref "U4") (pin "12") (pinfunction "G_12") (pintype "input"))
      (node (ref "U4") (pin "13") (pinfunction "H_13") (pintype "input"))
      (node (ref "U4") (pin "14") (pinfunction "VDD_14") (pintype "power_in"))
      (node (ref "U4") (pin "5") (pinfunction "C_5") (pintype "input"))
      (node (ref "U4") (pin "6") (pinfunction "D_6") (pintype "output"))
      (node (ref "U4") (pin "8") (pinfunction "E_8") (pintype "input"))
      (node (ref "U4") (pin "9") (pinfunction "F_9") (pintype "input"))
      (node (ref "U5") (pin "5") (pinfunction "V+_5") (pintype "power_in"))
      (node (ref "U6") (pin "3") (pinfunction "V+_3") (pintype "power_in"))
      (node (ref "U7") (pin "5") (pinfunction "V+_5") (pintype "power_in"))
      (node (ref "U8") (pin "3") (pinfunction "V+_3") (pintype "power_in"))
      (node (ref "U9") (pin "16") (pinfunction "VDD_16") (pintype "power_in"))
      (node (ref "U9") (pin "5") (pinfunction "ENABLE_5") (pintype "input"))
    )
    (net (code "43") (name "VCC12V") (class "Default")
      (node (ref "C1") (pin "1") (pinfunction "1_1") (pintype "passive"))
      (node (ref "J1") (pin "1") (pinfunction "1_1") (pintype "passive"))
      (node (ref "U11") (pin "3") (pinfunction "IN_3") (pintype "power_in"))
    )
    (net (code "44") (name "unconnected-(U2F-~{6Y}-Pad12)") (class "Default")
      (node (ref "U2") (pin "12") (pinfunction "~{6Y}_12") (pintype "output+no_connect"))
    )
    (net (code "45") (name "unconnected-(U3C-L-Pad10)") (class "Default")
      (node (ref "U3") (pin "10") (pinfunction "L_10") (pintype "output+no_connect"))
    )
    (net (code "46") (name "unconnected-(U3D-M-Pad11)") (class "Default")
      (node (ref "U3") (pin "11") (pinfunction "M_11") (pintype "output+no_connect"))
    )
    (net (code "47") (name "unconnected-(U4-K-Pad4)") (class "Default")
      (node (ref "U4") (pin "4") (pinfunction "K_4") (pintype "input+no_connect"))
    )
    (net (code "48") (name "unconnected-(U4-L-Pad10)") (class "Default")
      (node (ref "U4") (pin "10") (pinfunction "L_10") (pintype "output+no_connect"))
    )
    (net (code "49") (name "unconnected-(U4-M-Pad11)") (class "Default")
      (node (ref "U4") (pin "11") (pinfunction "M_11") (pintype "output+no_connect"))
    )
    (net (code "50") (name "unconnected-(U8C-OUT3-Pad14)") (class "Default")
      (node (ref "U8") (pin "14") (pinfunction "OUT3_14") (pintype "output+no_connect"))
    )
    (net (code "51") (name "unconnected-(U8D-OUT4-Pad13)") (class "Default")
      (node (ref "U8") (pin "13") (pinfunction "OUT4_13") (pintype "output+no_connect"))
    )
    (net (code "52") (name "unconnected-(U9-NC-Pad2)") (class "Default")
      (node (ref "U9") (pin "2") (pinfunction "NC_2") (pintype "passive+no_connect"))
    )
    (net (code "53") (name "unconnected-(U9-Q2-Pad9)") (class "Default")
      (node (ref "U9") (pin "9") (pinfunction "Q2_9") (pintype "input+no_connect"))
    )
    (net (code "54") (name "unconnected-(U9-Q3-Pad10)") (class "Default")
      (node (ref "U9") (pin "10") (pinfunction "Q3_10") (pintype "input+no_connect"))
    )
    (net (code "55") (name "unconnected-(U9-Q4-Pad1)") (class "Default")
      (node (ref "U9") (pin "1") (pinfunction "Q4_1") (pintype "output+no_connect"))
    )
  )
)
